# Motor_Drive.net
KiCad netlist of a schematic drawn in Altium Designer
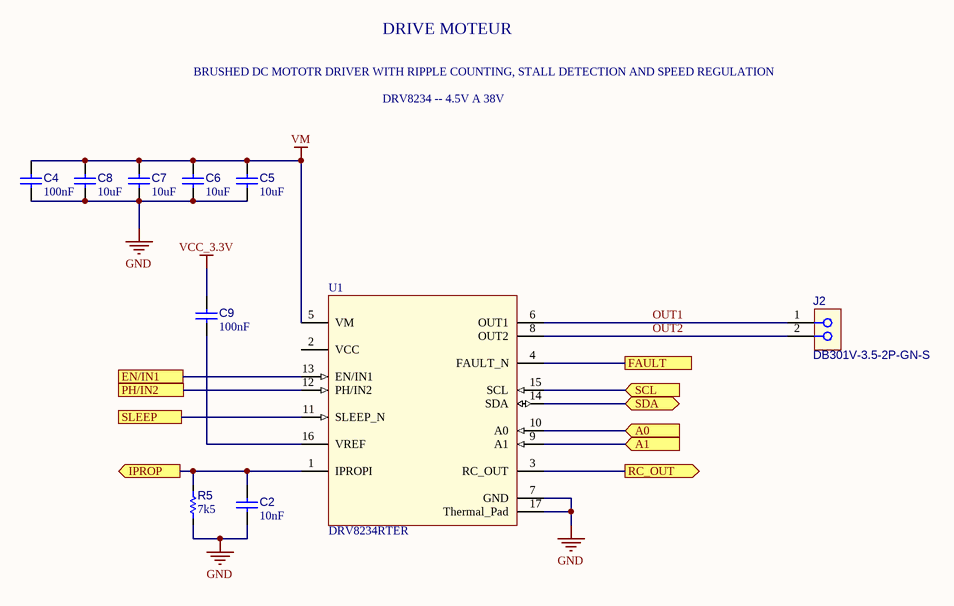
[diagram p0: Motor_Drive.SchDoc]

(export (version "E")
  (design (tool "Eeschema 10.0.6"))
  (components
    (comp (ref "C2")
      (value "10nF")
      (footprint "C_1608[0603]")
      (description "Capacitor type 1")
      (fields (field (name "TOLERANCE") "10%") (field (name "Comment") "CAP CER 10nF 50V 0603"))
      (libsource (lib "TEP_243-Altium_DBLib") (part "capacitor"))
    )
    (comp (ref "C4")
      (value "100nF")
      (footprint "C_2012[0805]")
      (description "Capacitor type 1")
      (fields (field (name "TOLERANCE") "10%") (field (name "Comment") "CAP CER 100nF 50V 0805"))
      (libsource (lib "TEP_243-Altium_DBLib") (part "capacitor"))
    )
    (comp (ref "C5")
      (value "10uF")
      (footprint "C_2012[0805]")
      (description "Capacitor type 1")
      (fields (field (name "TOLERANCE") "10%") (field (name "Comment") "CAP CER 10uF 10V X7R 0805"))
      (libsource (lib "TEP_243-Altium_DBLib") (part "capacitor"))
    )
    (comp (ref "C6")
      (value "10uF")
      (footprint "C_2012[0805]")
      (description "Capacitor type 1")
      (fields (field (name "TOLERANCE") "10%") (field (name "Comment") "CAP CER 10uF 10V X7R 0805"))
      (libsource (lib "TEP_243-Altium_DBLib") (part "capacitor"))
    )
    (comp (ref "C7")
      (value "10uF")
      (footprint "C_2012[0805]")
      (description "Capacitor type 1")
      (fields (field (name "TOLERANCE") "10%") (field (name "Comment") "CAP CER 10uF 10V X7R 0805"))
      (libsource (lib "TEP_243-Altium_DBLib") (part "capacitor"))
    )
    (comp (ref "C8")
      (value "10uF")
      (footprint "C_2012[0805]")
      (description "Capacitor type 1")
      (fields (field (name "TOLERANCE") "10%") (field (name "Comment") "CAP CER 10uF 10V X7R 0805"))
      (libsource (lib "TEP_243-Altium_DBLib") (part "capacitor"))
    )
    (comp (ref "C9")
      (value "100nF")
      (footprint "C_2012[0805]")
      (description "Capacitor type 1")
      (fields (field (name "TOLERANCE") "10%") (field (name "Comment") "CAP CER 100nF 50V 0805"))
      (libsource (lib "TEP_243-Altium_DBLib") (part "capacitor"))
    )
    (comp (ref "J2")
      (value "DB301V-3.5-2P-GN-S")
      (footprint "CONN_TERM_BLOCK_2POS_3mm5")
      (description "CONN TERM BLOCK 2POS 3.5mm pitch")
      (libsource (lib "TEP_243-AltiumLIB-Conn-TP-MH") (part "CONN-3MM5-2POS-TERM-BLOCK"))
    )
    (comp (ref "R5")
      (value "7k5")
      (footprint "R_1005[0402]")
      (description "Resistor type 1")
      (fields (field (name "TOLERANCE") "1%") (field (name "Comment") "Res 7k5 1% 0402"))
      (libsource (lib "TEP_243-Altium_DBLib") (part "resistor"))
    )
    (comp (ref "U1")
      (value "DRV8234RTER")
      (footprint "U_WQFN50P300X300-16")
      (libsource (lib "TEP_243-Altium_Library") (part "U_DRV8234"))
    )
  )
  (nets
    (net (code "1") (name "/A0") (class "Default")
      (node (ref "U1") (pin "10") (pinfunction "A0_10") (pintype "input"))
    )
    (net (code "2") (name "/A1") (class "Default")
      (node (ref "U1") (pin "9") (pinfunction "A1_9") (pintype "input"))
    )
    (net (code "3") (name "/EN{slash}IN1") (class "Default")
      (node (ref "U1") (pin "13") (pinfunction "EN/IN1_13") (pintype "input"))
    )
    (net (code "4") (name "/FAULT") (class "Default")
      (node (ref "U1") (pin "4") (pinfunction "FAULT_N_4") (pintype "open_collector"))
    )
    (net (code "5") (name "/IPROP") (class "Default")
      (node (ref "C2") (pin "2") (pinfunction "2_2") (pintype "passive"))
      (node (ref "R5") (pin "2") (pinfunction "2_2") (pintype "passive"))
      (node (ref "U1") (pin "1") (pinfunction "IPROPI_1") (pintype "passive"))
    )
    (net (code "6") (name "/OUT1") (class "Default")
      (node (ref "J2") (pin "1") (pinfunction "1_1") (pintype "passive"))
      (node (ref "U1") (pin "6") (pinfunction "OUT1_6") (pintype "passive"))
    )
    (net (code "7") (name "/OUT2") (class "Default")
      (node (ref "J2") (pin "2") (pinfunction "2_2") (pintype "passive"))
      (node (ref "U1") (pin "8") (pinfunction "OUT2_8") (pintype "passive"))
    )
    (net (code "8") (name "/PH{slash}IN2") (class "Default")
      (node (ref "U1") (pin "12") (pinfunction "PH/IN2_12") (pintype "input"))
    )
    (net (code "9") (name "/RC_OUT") (class "Default")
      (node (ref "U1") (pin "3") (pinfunction "RC_OUT_3") (pintype "open_collector"))
    )
    (net (code "10") (name "/SCL") (class "Default")
      (node (ref "U1") (pin "15") (pinfunction "SCL_15") (pintype "input"))
    )
    (net (code "11") (name "/SDA") (class "Default")
      (node (ref "U1") (pin "14") (pinfunction "SDA_14") (pintype "bidirectional"))
    )
    (net (code "12") (name "/SLEEP") (class "Default")
      (node (ref "U1") (pin "11") (pinfunction "SLEEP_N_11") (pintype "input"))
    )
    (net (code "13") (name "GND") (class "Default")
      (node (ref "C2") (pin "1") (pinfunction "1_1") (pintype "passive"))
      (node (ref "C4") (pin "1") (pinfunction "1_1") (pintype "passive"))
      (node (ref "C5") (pin "2") (pinfunction "2_2") (pintype "passive"))
      (node (ref "C6") (pin "1") (pinfunction "1_1") (pintype "passive"))
      (node (ref "C7") (pin "2") (pinfunction "2_2") (pintype "passive"))
      (node (ref "C8") (pin "1") (pinfunction "1_1") (pintype "passive"))
      (node (ref "R5") (pin "1") (pinfunction "1_1") (pintype "passive"))
      (node (ref "U1") (pin "17") (pinfunction "Thermal_Pad_17") (pintype "power_in"))
      (node (ref "U1") (pin "7") (pinfunction "GND_7") (pintype "power_in"))
    )
    (net (code "14") (name "Net-(U1-VREF)") (class "Default")
      (node (ref "C9") (pin "1") (pinfunction "1_1") (pintype "passive"))
      (node (ref "U1") (pin "16") (pinfunction "VREF_16") (pintype "passive"))
    )
    (net (code "15") (name "VCC_3.3V") (class "Default")
      (node (ref "C9") (pin "2") (pinfunction "2_2") (pintype "passive"))
    )
    (net (code "16") (name "VM") (class "Default")
      (node (ref "C4") (pin "2") (pinfunction "2_2") (pintype "passive"))
      (node (ref "C5") (pin "1") (pinfunction "1_1") (pintype "passive"))
      (node (ref "C6") (pin "2") (pinfunction "2_2") (pintype "passive"))
      (node (ref "C7") (pin "1") (pinfunction "1_1") (pintype "passive"))
      (node (ref "C8") (pin "2") (pinfunction "2_2") (pintype "passive"))
      (node (ref "U1") (pin "5") (pinfunction "VM_5") (pintype "power_in"))
    )
    (net (code "17") (name "unconnected-(U1-VCC-Pad2)") (class "Default")
      (node (ref "U1") (pin "2") (pinfunction "VCC_2") (pintype "power_in"))
    )
  )
)
